# interfaz_1.net
KiCad netlist of a schematic drawn in EAGLE
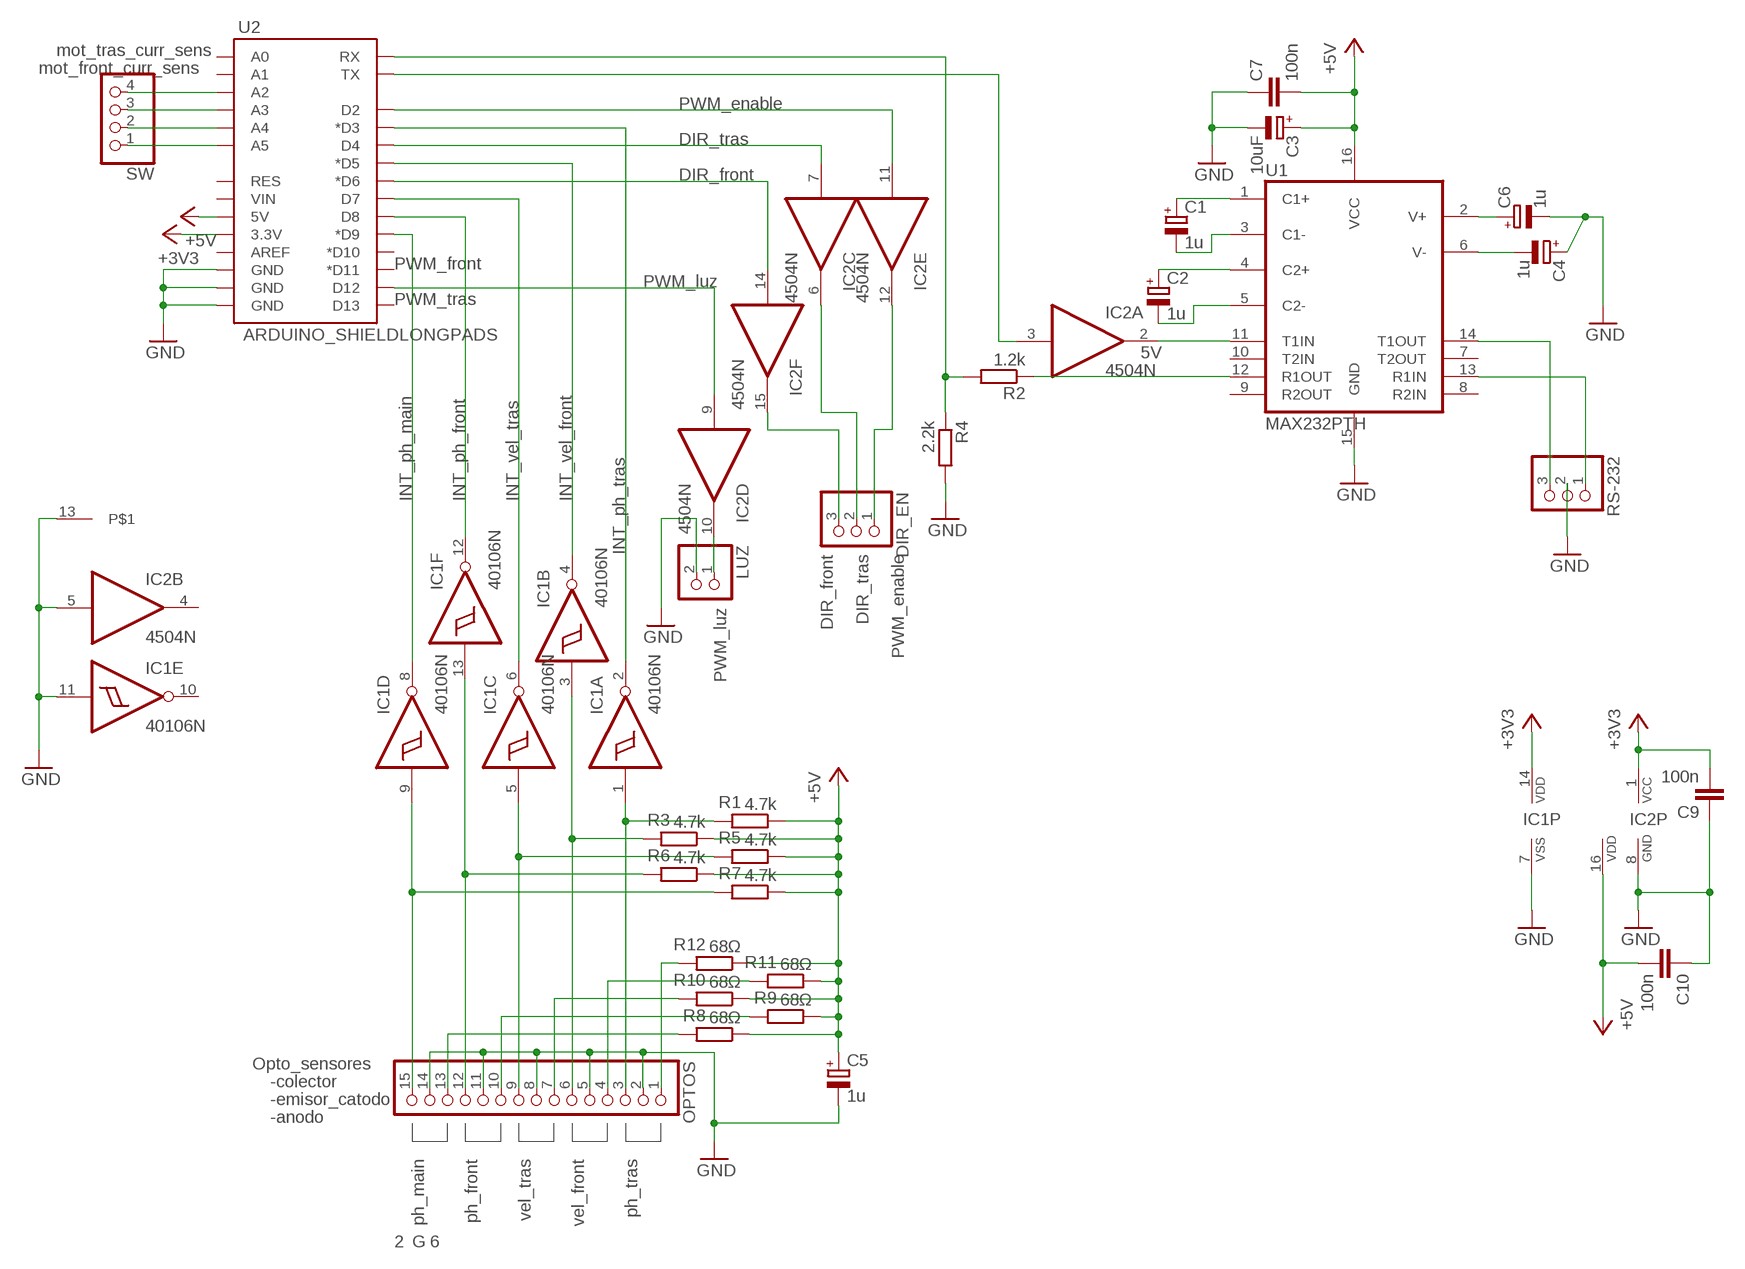
[diagram p0: schematic, sheet 1]

(export (version "E")
  (design (tool "Eeschema 10.0.6"))
  (components
    (comp (ref "C1")
      (value "1u")
      (footprint "eagle-import:E2-4")
      (libsource (lib "eagle-import") (part "CPOL-EUE2-4"))
    )
    (comp (ref "C2")
      (value "1u")
      (footprint "eagle-import:E2-4")
      (libsource (lib "eagle-import") (part "CPOL-EUE2-4"))
    )
    (comp (ref "C3")
      (value "10uF")
      (footprint "eagle-import:E2-4")
      (libsource (lib "eagle-import") (part "CPOL-EUE2-4"))
    )
    (comp (ref "C4")
      (value "1u")
      (footprint "eagle-import:E2-4")
      (libsource (lib "eagle-import") (part "CPOL-EUE2-4"))
    )
    (comp (ref "C5")
      (value "1u")
      (footprint "eagle-import:E2-4")
      (libsource (lib "eagle-import") (part "CPOL-EUE2-4"))
    )
    (comp (ref "C6")
      (value "1u")
      (footprint "eagle-import:E2-4")
      (libsource (lib "eagle-import") (part "CPOL-EUE2-4"))
    )
    (comp (ref "C7")
      (value "100n")
      (footprint "eagle-import:C025-025X050")
      (libsource (lib "eagle-import") (part "C-EU025-025X050"))
    )
    (comp (ref "C9")
      (value "100n")
      (footprint "eagle-import:C025-025X050")
      (libsource (lib "eagle-import") (part "C-EU025-025X050"))
    )
    (comp (ref "C10")
      (value "100n")
      (footprint "eagle-import:C025-025X050")
      (libsource (lib "eagle-import") (part "C-EU025-025X050"))
    )
    (comp (ref "DIR_EN")
      (value "PINHD-1X3")
      (footprint "eagle-import:1X03")
      (libsource (lib "eagle-import") (part "PINHD-1X3"))
    )
    (comp (ref "IC1")
      (value "40106N")
      (footprint "eagle-import:DIL14")
      (libsource (lib "eagle-import") (part "40106N"))
    )
    (comp (ref "IC2")
      (value "4504N")
      (footprint "eagle-import:DIL16")
      (libsource (lib "eagle-import") (part "4504N"))
    )
    (comp (ref "LUZ")
      (value "PINHD-1X2")
      (footprint "eagle-import:1X02")
      (libsource (lib "eagle-import") (part "PINHD-1X2"))
    )
    (comp (ref "OPTOS")
      (value "PINHD-1X15")
      (footprint "eagle-import:1X15")
      (libsource (lib "eagle-import") (part "PINHD-1X15"))
    )
    (comp (ref "R1")
      (value "4.7k")
      (footprint "eagle-import:0204_5")
      (libsource (lib "eagle-import") (part "R-EU_0204/5"))
    )
    (comp (ref "R2")
      (value "1.2k")
      (footprint "eagle-import:0204_5")
      (libsource (lib "eagle-import") (part "R-EU_0204/5"))
    )
    (comp (ref "R3")
      (value "4.7k")
      (footprint "eagle-import:0204_5")
      (libsource (lib "eagle-import") (part "R-EU_0204/5"))
    )
    (comp (ref "R4")
      (value "2.2k")
      (footprint "eagle-import:0204_5")
      (libsource (lib "eagle-import") (part "R-EU_0204/5"))
    )
    (comp (ref "R5")
      (value "4.7k")
      (footprint "eagle-import:0204_5")
      (libsource (lib "eagle-import") (part "R-EU_0204/5"))
    )
    (comp (ref "R6")
      (value "4.7k")
      (footprint "eagle-import:0204_5")
      (libsource (lib "eagle-import") (part "R-EU_0204/5"))
    )
    (comp (ref "R7")
      (value "4.7k")
      (footprint "eagle-import:0204_5")
      (libsource (lib "eagle-import") (part "R-EU_0204/5"))
    )
    (comp (ref "R8")
      (value "68Ω")
      (footprint "eagle-import:0204_5")
      (libsource (lib "eagle-import") (part "R-EU_0204/5"))
    )
    (comp (ref "R9")
      (value "68Ω")
      (footprint "eagle-import:0204_5")
      (libsource (lib "eagle-import") (part "R-EU_0204/5"))
    )
    (comp (ref "R10")
      (value "68Ω")
      (footprint "eagle-import:0204_5")
      (libsource (lib "eagle-import") (part "R-EU_0204/5"))
    )
    (comp (ref "R11")
      (value "68Ω")
      (footprint "eagle-import:0204_5")
      (libsource (lib "eagle-import") (part "R-EU_0204/5"))
    )
    (comp (ref "R12")
      (value "68Ω")
      (footprint "eagle-import:0204_5")
      (libsource (lib "eagle-import") (part "R-EU_0204/5"))
    )
    (comp (ref "RS-232")
      (value "PINHD-1X3")
      (footprint "eagle-import:1X03")
      (libsource (lib "eagle-import") (part "PINHD-1X3"))
    )
    (comp (ref "SW")
      (value "PINHD-1X4")
      (footprint "eagle-import:1X04")
      (libsource (lib "eagle-import") (part "PINHD-1X4"))
    )
    (comp (ref "U1")
      (value "MAX232PTH")
      (footprint "eagle-import:DIL16")
      (libsource (lib "eagle-import") (part "MAX232PTH"))
    )
    (comp (ref "U2")
      (value "ARDUINO_SHIELDLONGPADS")
      (footprint "eagle-import:DUEMILANOVE_SHIELD_LONGPADS")
      (libsource (lib "eagle-import") (part "ARDUINO_SHIELDLONGPADS"))
    )
  )
  (nets
    (net (code "1") (name "+3V3") (class "Default")
      (node (ref "C9") (pin "2") (pinfunction "2_2") (pintype "passive"))
      (node (ref "IC1") (pin "14") (pinfunction "VDD_14") (pintype "power_in"))
      (node (ref "IC2") (pin "1") (pinfunction "VCC_1") (pintype "power_in"))
      (node (ref "U2") (pin "3.3V") (pinfunction "3.3V_3.3V") (pintype "bidirectional"))
    )
    (net (code "2") (name "+5V") (class "Default")
      (node (ref "C10") (pin "2") (pinfunction "2_2") (pintype "passive"))
      (node (ref "C3") (pin "+") (pinfunction "+_+") (pintype "passive"))
      (node (ref "C5") (pin "+") (pinfunction "+_+") (pintype "passive"))
      (node (ref "C7") (pin "2") (pinfunction "2_2") (pintype "passive"))
      (node (ref "IC2") (pin "16") (pinfunction "VDD_16") (pintype "power_in"))
      (node (ref "R1") (pin "1") (pinfunction "1_1") (pintype "passive"))
      (node (ref "R10") (pin "1") (pinfunction "1_1") (pintype "passive"))
      (node (ref "R11") (pin "1") (pinfunction "1_1") (pintype "passive"))
      (node (ref "R12") (pin "1") (pinfunction "1_1") (pintype "passive"))
      (node (ref "R3") (pin "1") (pinfunction "1_1") (pintype "passive"))
      (node (ref "R5") (pin "1") (pinfunction "1_1") (pintype "passive"))
      (node (ref "R6") (pin "1") (pinfunction "1_1") (pintype "passive"))
      (node (ref "R7") (pin "1") (pinfunction "1_1") (pintype "passive"))
      (node (ref "R8") (pin "1") (pinfunction "1_1") (pintype "passive"))
      (node (ref "R9") (pin "1") (pinfunction "1_1") (pintype "passive"))
      (node (ref "U1") (pin "16") (pinfunction "VCC_16") (pintype "bidirectional"))
      (node (ref "U2") (pin "5V") (pinfunction "5V_5V") (pintype "bidirectional"))
    )
    (net (code "3") (name "GND") (class "Default")
      (node (ref "C10") (pin "1") (pinfunction "1_1") (pintype "passive"))
      (node (ref "C3") (pin "-") (pinfunction "-_-") (pintype "passive"))
      (node (ref "C4") (pin "+") (pinfunction "+_+") (pintype "passive"))
      (node (ref "C5") (pin "-") (pinfunction "-_-") (pintype "passive"))
      (node (ref "C6") (pin "-") (pinfunction "-_-") (pintype "passive"))
      (node (ref "C7") (pin "1") (pinfunction "1_1") (pintype "passive"))
      (node (ref "C9") (pin "1") (pinfunction "1_1") (pintype "passive"))
      (node (ref "IC1") (pin "11") (pinfunction "I_11") (pintype "input"))
      (node (ref "IC1") (pin "7") (pinfunction "VSS_7") (pintype "power_in"))
      (node (ref "IC2") (pin "13") (pinfunction "P$1_13") (pintype "bidirectional"))
      (node (ref "IC2") (pin "5") (pinfunction "I_5") (pintype "input"))
      (node (ref "IC2") (pin "8") (pinfunction "GND_8") (pintype "power_in"))
      (node (ref "LUZ") (pin "2") (pinfunction "2_2") (pintype "passive"))
      (node (ref "OPTOS") (pin "11") (pinfunction "11_11") (pintype "passive"))
      (node (ref "OPTOS") (pin "14") (pinfunction "14_14") (pintype "passive"))
      (node (ref "OPTOS") (pin "2") (pinfunction "2_2") (pintype "passive"))
      (node (ref "OPTOS") (pin "5") (pinfunction "5_5") (pintype "passive"))
      (node (ref "OPTOS") (pin "8") (pinfunction "8_8") (pintype "passive"))
      (node (ref "R4") (pin "2") (pinfunction "2_2") (pintype "passive"))
      (node (ref "RS-232") (pin "2") (pinfunction "2_2") (pintype "passive"))
      (node (ref "U1") (pin "15") (pinfunction "GND_15") (pintype "bidirectional"))
      (node (ref "U2") (pin "GND@0") (pinfunction "GND_GND@0") (pintype "bidirectional"))
      (node (ref "U2") (pin "GND@1") (pinfunction "GND_GND@1") (pintype "bidirectional"))
      (node (ref "U2") (pin "GND@2") (pinfunction "GND_GND@2") (pintype "bidirectional"))
    )
    (net (code "4") (name "Net-(IC1A-I)") (class "Default")
      (node (ref "IC1") (pin "1") (pinfunction "I_1") (pintype "input"))
      (node (ref "OPTOS") (pin "3") (pinfunction "3_3") (pintype "passive"))
      (node (ref "R1") (pin "2") (pinfunction "2_2") (pintype "passive"))
    )
    (net (code "5") (name "Net-(IC1A-O)") (class "Default")
      (node (ref "IC1") (pin "2") (pinfunction "O_2") (pintype "output"))
      (node (ref "U2") (pin "D3") (pinfunction "*D3_D3") (pintype "bidirectional"))
    )
    (net (code "6") (name "Net-(IC1B-I)") (class "Default")
      (node (ref "IC1") (pin "3") (pinfunction "I_3") (pintype "input"))
      (node (ref "OPTOS") (pin "6") (pinfunction "6_6") (pintype "passive"))
      (node (ref "R3") (pin "2") (pinfunction "2_2") (pintype "passive"))
    )
    (net (code "7") (name "Net-(IC1B-O)") (class "Default")
      (node (ref "IC1") (pin "4") (pinfunction "O_4") (pintype "output"))
      (node (ref "U2") (pin "D5") (pinfunction "*D5_D5") (pintype "bidirectional"))
    )
    (net (code "8") (name "Net-(IC1C-I)") (class "Default")
      (node (ref "IC1") (pin "5") (pinfunction "I_5") (pintype "input"))
      (node (ref "OPTOS") (pin "9") (pinfunction "9_9") (pintype "passive"))
      (node (ref "R5") (pin "2") (pinfunction "2_2") (pintype "passive"))
    )
    (net (code "9") (name "Net-(IC1C-O)") (class "Default")
      (node (ref "IC1") (pin "6") (pinfunction "O_6") (pintype "output"))
      (node (ref "U2") (pin "D7") (pinfunction "D7_D7") (pintype "bidirectional"))
    )
    (net (code "10") (name "Net-(IC1D-I)") (class "Default")
      (node (ref "IC1") (pin "9") (pinfunction "I_9") (pintype "input"))
      (node (ref "OPTOS") (pin "15") (pinfunction "15_15") (pintype "passive"))
      (node (ref "R7") (pin "2") (pinfunction "2_2") (pintype "passive"))
    )
    (net (code "11") (name "Net-(IC1D-O)") (class "Default")
      (node (ref "IC1") (pin "8") (pinfunction "O_8") (pintype "output"))
      (node (ref "U2") (pin "D9") (pinfunction "*D9_D9") (pintype "bidirectional"))
    )
    (net (code "12") (name "Net-(IC1F-I)") (class "Default")
      (node (ref "IC1") (pin "13") (pinfunction "I_13") (pintype "input"))
      (node (ref "OPTOS") (pin "12") (pinfunction "12_12") (pintype "passive"))
      (node (ref "R6") (pin "2") (pinfunction "2_2") (pintype "passive"))
    )
    (net (code "13") (name "Net-(IC1F-O)") (class "Default")
      (node (ref "IC1") (pin "12") (pinfunction "O_12") (pintype "output"))
      (node (ref "U2") (pin "D8") (pinfunction "D8_D8") (pintype "bidirectional"))
    )
    (net (code "14") (name "Net-(IC2A-I)") (class "Default")
      (node (ref "IC2") (pin "3") (pinfunction "I_3") (pintype "input"))
      (node (ref "U2") (pin "TX") (pinfunction "TX_TX") (pintype "bidirectional"))
    )
    (net (code "15") (name "Net-(IC2A-O)") (class "Default")
      (node (ref "IC2") (pin "2") (pinfunction "O_2") (pintype "output"))
      (node (ref "U1") (pin "11") (pinfunction "T1IN_11") (pintype "input"))
    )
    (net (code "16") (name "Net-(IC2C-I)") (class "Default")
      (node (ref "IC2") (pin "7") (pinfunction "I_7") (pintype "input"))
      (node (ref "U2") (pin "D4") (pinfunction "D4_D4") (pintype "bidirectional"))
    )
    (net (code "17") (name "Net-(IC2C-O)") (class "Default")
      (node (ref "DIR_EN") (pin "2") (pinfunction "2_2") (pintype "passive"))
      (node (ref "IC2") (pin "6") (pinfunction "O_6") (pintype "output"))
    )
    (net (code "18") (name "Net-(IC2D-I)") (class "Default")
      (node (ref "IC2") (pin "9") (pinfunction "I_9") (pintype "input"))
      (node (ref "U2") (pin "D12") (pinfunction "D12_D12") (pintype "bidirectional"))
    )
    (net (code "19") (name "Net-(IC2D-O)") (class "Default")
      (node (ref "IC2") (pin "10") (pinfunction "O_10") (pintype "output"))
      (node (ref "LUZ") (pin "1") (pinfunction "1_1") (pintype "passive"))
    )
    (net (code "20") (name "Net-(IC2E-I)") (class "Default")
      (node (ref "IC2") (pin "11") (pinfunction "I_11") (pintype "input"))
      (node (ref "U2") (pin "D2") (pinfunction "D2_D2") (pintype "bidirectional"))
    )
    (net (code "21") (name "Net-(IC2E-O)") (class "Default")
      (node (ref "DIR_EN") (pin "1") (pinfunction "1_1") (pintype "passive"))
      (node (ref "IC2") (pin "12") (pinfunction "O_12") (pintype "output"))
    )
    (net (code "22") (name "Net-(IC2F-I)") (class "Default")
      (node (ref "IC2") (pin "14") (pinfunction "I_14") (pintype "input"))
      (node (ref "U2") (pin "D6") (pinfunction "*D6_D6") (pintype "bidirectional"))
    )
    (net (code "23") (name "Net-(IC2F-O)") (class "Default")
      (node (ref "DIR_EN") (pin "3") (pinfunction "3_3") (pintype "passive"))
      (node (ref "IC2") (pin "15") (pinfunction "O_15") (pintype "output"))
    )
    (net (code "24") (name "Net-(OPTOS-Pad1)") (class "Default")
      (node (ref "OPTOS") (pin "1") (pinfunction "1_1") (pintype "passive"))
      (node (ref "R12") (pin "2") (pinfunction "2_2") (pintype "passive"))
    )
    (net (code "25") (name "Net-(OPTOS-Pad4)") (class "Default")
      (node (ref "OPTOS") (pin "4") (pinfunction "4_4") (pintype "passive"))
      (node (ref "R11") (pin "2") (pinfunction "2_2") (pintype "passive"))
    )
    (net (code "26") (name "Net-(OPTOS-Pad7)") (class "Default")
      (node (ref "OPTOS") (pin "7") (pinfunction "7_7") (pintype "passive"))
      (node (ref "R10") (pin "2") (pinfunction "2_2") (pintype "passive"))
    )
    (net (code "27") (name "Net-(OPTOS-Pad10)") (class "Default")
      (node (ref "OPTOS") (pin "10") (pinfunction "10_10") (pintype "passive"))
      (node (ref "R9") (pin "2") (pinfunction "2_2") (pintype "passive"))
    )
    (net (code "28") (name "Net-(OPTOS-Pad13)") (class "Default")
      (node (ref "OPTOS") (pin "13") (pinfunction "13_13") (pintype "passive"))
      (node (ref "R8") (pin "2") (pinfunction "2_2") (pintype "passive"))
    )
    (net (code "29") (name "Net-(R2-Pad2)") (class "Default")
      (node (ref "R2") (pin "2") (pinfunction "2_2") (pintype "passive"))
      (node (ref "R4") (pin "1") (pinfunction "1_1") (pintype "passive"))
      (node (ref "U2") (pin "RX") (pinfunction "RX_RX") (pintype "bidirectional"))
    )
    (net (code "30") (name "Net-(SW-Pad1)") (class "Default")
      (node (ref "SW") (pin "1") (pinfunction "1_1") (pintype "passive"))
      (node (ref "U2") (pin "A5") (pinfunction "A5_A5") (pintype "bidirectional"))
    )
    (net (code "31") (name "Net-(SW-Pad2)") (class "Default")
      (node (ref "SW") (pin "2") (pinfunction "2_2") (pintype "passive"))
      (node (ref "U2") (pin "A4") (pinfunction "A4_A4") (pintype "bidirectional"))
    )
    (net (code "32") (name "Net-(SW-Pad3)") (class "Default")
      (node (ref "SW") (pin "3") (pinfunction "3_3") (pintype "passive"))
      (node (ref "U2") (pin "A3") (pinfunction "A3_A3") (pintype "bidirectional"))
    )
    (net (code "33") (name "Net-(SW-Pad4)") (class "Default")
      (node (ref "SW") (pin "4") (pinfunction "4_4") (pintype "passive"))
      (node (ref "U2") (pin "A2") (pinfunction "A2_A2") (pintype "bidirectional"))
    )
    (net (code "34") (name "Net-(U1-C1+)") (class "Default")
      (node (ref "C1") (pin "+") (pinfunction "+_+") (pintype "passive"))
      (node (ref "U1") (pin "1") (pinfunction "C1+_1") (pintype "bidirectional"))
    )
    (net (code "35") (name "Net-(U1-C1-)") (class "Default")
      (node (ref "C1") (pin "-") (pinfunction "-_-") (pintype "passive"))
      (node (ref "U1") (pin "3") (pinfunction "C1-_3") (pintype "bidirectional"))
    )
    (net (code "36") (name "Net-(U1-C2+)") (class "Default")
      (node (ref "C2") (pin "+") (pinfunction "+_+") (pintype "passive"))
      (node (ref "U1") (pin "4") (pinfunction "C2+_4") (pintype "bidirectional"))
    )
    (net (code "37") (name "Net-(U1-C2-)") (class "Default")
      (node (ref "C2") (pin "-") (pinfunction "-_-") (pintype "passive"))
      (node (ref "U1") (pin "5") (pinfunction "C2-_5") (pintype "bidirectional"))
    )
    (net (code "38") (name "Net-(U1-R1IN)") (class "Default")
      (node (ref "RS-232") (pin "1") (pinfunction "1_1") (pintype "passive"))
      (node (ref "U1") (pin "13") (pinfunction "R1IN_13") (pintype "input"))
    )
    (net (code "39") (name "Net-(U1-R1OUT)") (class "Default")
      (node (ref "R2") (pin "1") (pinfunction "1_1") (pintype "passive"))
      (node (ref "U1") (pin "12") (pinfunction "R1OUT_12") (pintype "output"))
    )
    (net (code "40") (name "Net-(U1-T1OUT)") (class "Default")
      (node (ref "RS-232") (pin "3") (pinfunction "3_3") (pintype "passive"))
      (node (ref "U1") (pin "14") (pinfunction "T1OUT_14") (pintype "output"))
    )
    (net (code "41") (name "Net-(U1-V+)") (class "Default")
      (node (ref "C6") (pin "+") (pinfunction "+_+") (pintype "passive"))
      (node (ref "U1") (pin "2") (pinfunction "V+_2") (pintype "bidirectional"))
    )
    (net (code "42") (name "Net-(U1-V-)") (class "Default")
      (node (ref "C4") (pin "-") (pinfunction "-_-") (pintype "passive"))
      (node (ref "U1") (pin "6") (pinfunction "V-_6") (pintype "bidirectional"))
    )
    (net (code "43") (name "unconnected-(IC1E-O-Pad10)") (class "Default")
      (node (ref "IC1") (pin "10") (pinfunction "O_10") (pintype "output"))
    )
    (net (code "44") (name "unconnected-(IC2B-O-Pad4)") (class "Default")
      (node (ref "IC2") (pin "4") (pinfunction "O_4") (pintype "output"))
    )
    (net (code "45") (name "unconnected-(U1-R2IN-Pad8)") (class "Default")
      (node (ref "U1") (pin "8") (pinfunction "R2IN_8") (pintype "input"))
    )
    (net (code "46") (name "unconnected-(U1-R2OUT-Pad9)") (class "Default")
      (node (ref "U1") (pin "9") (pinfunction "R2OUT_9") (pintype "output"))
    )
    (net (code "47") (name "unconnected-(U1-T2IN-Pad10)") (class "Default")
      (node (ref "U1") (pin "10") (pinfunction "T2IN_10") (pintype "input"))
    )
    (net (code "48") (name "unconnected-(U1-T2OUT-Pad7)") (class "Default")
      (node (ref "U1") (pin "7") (pinfunction "T2OUT_7") (pintype "output"))
    )
    (net (code "49") (name "unconnected-(U2-*D10-PadD10)") (class "Default")
      (node (ref "U2") (pin "D10") (pinfunction "*D10_D10") (pintype "bidirectional"))
    )
    (net (code "50") (name "unconnected-(U2-*D11-PadD11)") (class "Default")
      (node (ref "U2") (pin "D11") (pinfunction "*D11_D11") (pintype "bidirectional"))
    )
    (net (code "51") (name "unconnected-(U2-PadA0)") (class "Default")
      (node (ref "U2") (pin "A0") (pinfunction "A0_A0") (pintype "bidirectional"))
    )
    (net (code "52") (name "unconnected-(U2-PadA1)") (class "Default")
      (node (ref "U2") (pin "A1") (pinfunction "A1_A1") (pintype "bidirectional"))
    )
    (net (code "53") (name "unconnected-(U2-PadAREF)") (class "Default")
      (node (ref "U2") (pin "AREF") (pinfunction "AREF_AREF") (pintype "bidirectional"))
    )
    (net (code "54") (name "unconnected-(U2-PadD13)") (class "Default")
      (node (ref "U2") (pin "D13") (pinfunction "D13_D13") (pintype "bidirectional"))
    )
    (net (code "55") (name "unconnected-(U2-PadRES)") (class "Default")
      (node (ref "U2") (pin "RES") (pinfunction "RES_RES") (pintype "bidirectional"))
    )
    (net (code "56") (name "unconnected-(U2-PadVIN)") (class "Default")
      (node (ref "U2") (pin "VIN") (pinfunction "VIN_VIN") (pintype "bidirectional"))
    )
  )
)
